# nixie_main_controller_board_0_2_1.net
KiCad netlist of a schematic drawn in EAGLE
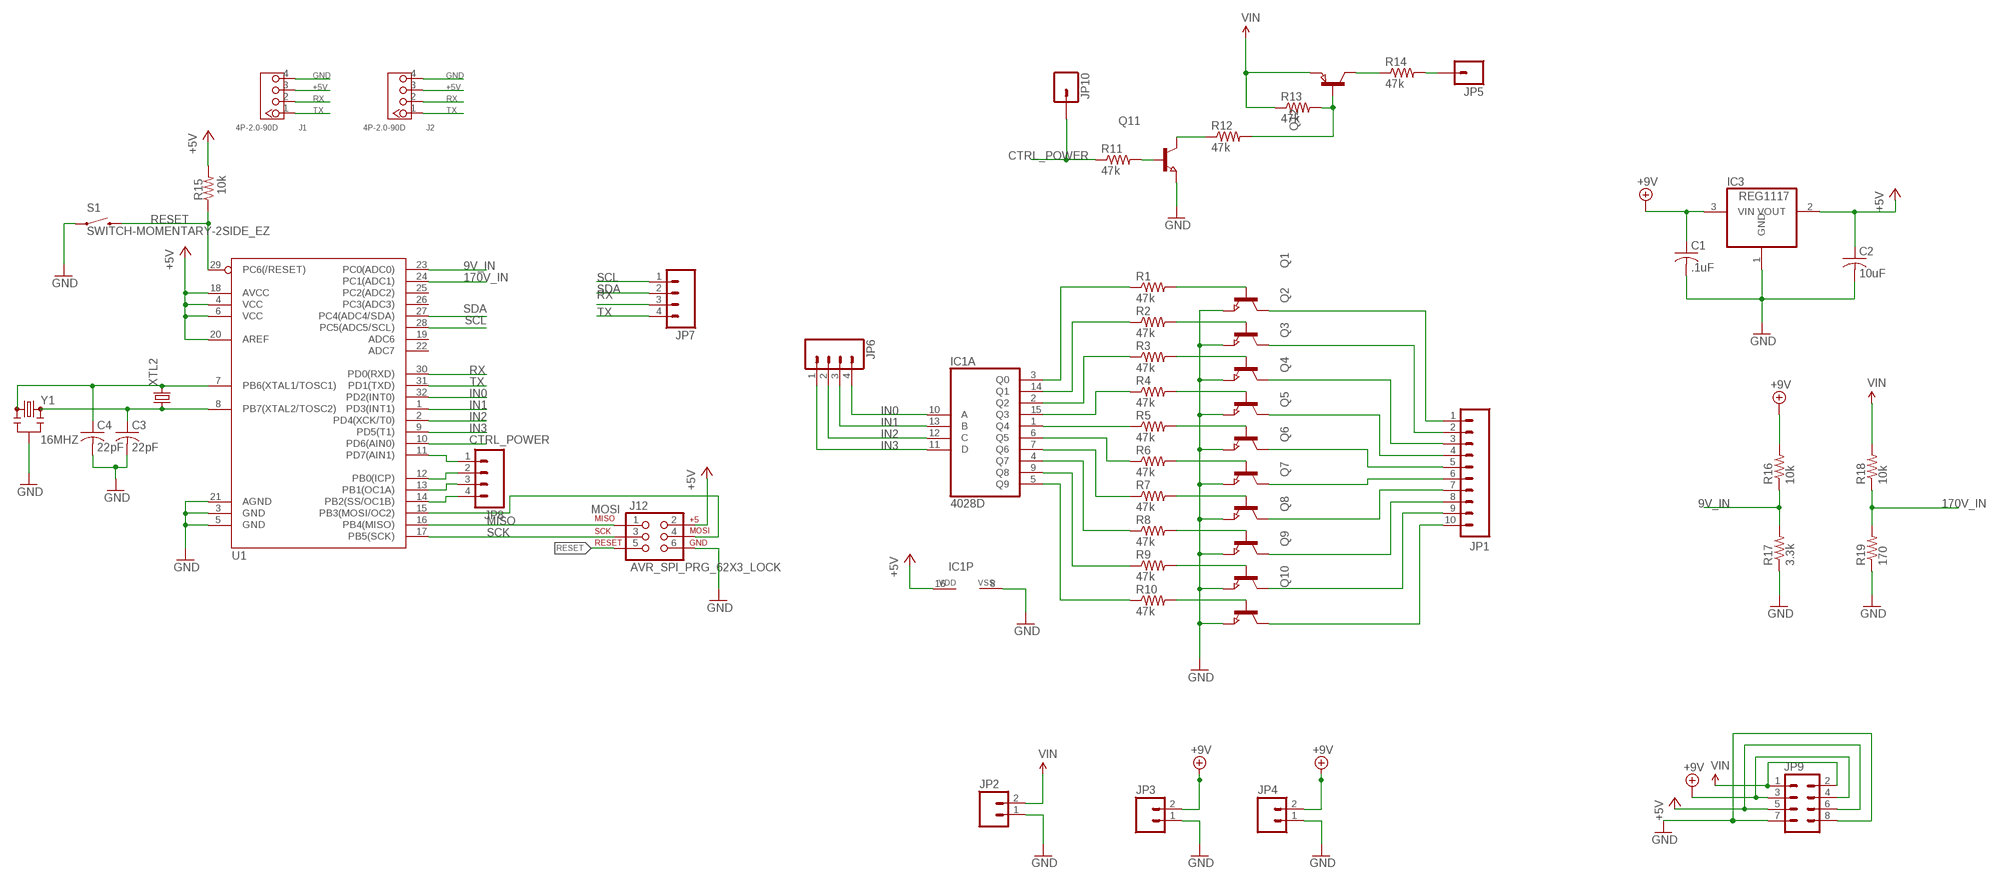
[diagram p0: schematic, sheet 1]

(export (version "E")
  (design (tool "Eeschema 10.0.6"))
  (components
    (comp (ref "C1")
      (value ".1uF")
      (footprint "eagle-import:C0603")
      (libsource (lib "eagle-import") (part "C-USC0603"))
    )
    (comp (ref "C2")
      (value "10uF")
      (footprint "eagle-import:C0805")
      (libsource (lib "eagle-import") (part "C-USC0805"))
    )
    (comp (ref "C3")
      (value "22pF")
      (footprint "eagle-import:C0603")
      (libsource (lib "eagle-import") (part "C-USC0603"))
    )
    (comp (ref "C4")
      (value "22pF")
      (footprint "eagle-import:C0603")
      (libsource (lib "eagle-import") (part "C-USC0603"))
    )
    (comp (ref "IC1")
      (value "4028D")
      (footprint "eagle-import:SO16")
      (libsource (lib "eagle-import") (part "4028D"))
    )
    (comp (ref "IC3")
      (value "REG1117")
      (footprint "eagle-import:SOT223")
      (libsource (lib "eagle-import") (part "REG1117"))
    )
    (comp (ref "J1")
      (value "4P-2.0-90D")
      (footprint "eagle-import:HW4-2.0-90D")
      (libsource (lib "eagle-import") (part "GROVE-CONNECTOR-DIP-90D(4P-2.0)"))
    )
    (comp (ref "J2")
      (value "4P-2.0-90D")
      (footprint "eagle-import:HW4-2.0-90D")
      (libsource (lib "eagle-import") (part "GROVE-CONNECTOR-DIP-90D(4P-2.0)"))
    )
    (comp (ref "J12")
      (value "AVR_SPI_PRG_62X3_LOCK")
      (footprint "eagle-import:2X3_LOCK")
      (libsource (lib "eagle-import") (part "AVR_SPI_PRG_62X3_LOCK"))
    )
    (comp (ref "JP1")
      (value "M10LOCK")
      (footprint "eagle-import:1X10_LOCK")
      (libsource (lib "eagle-import") (part "M10LOCK"))
    )
    (comp (ref "JP2")
      (value "M02LOCK")
      (footprint "eagle-import:1X02_LOCK")
      (libsource (lib "eagle-import") (part "M02LOCK"))
    )
    (comp (ref "JP3")
      (value "M02LOCK")
      (footprint "eagle-import:1X02_LOCK")
      (libsource (lib "eagle-import") (part "M02LOCK"))
    )
    (comp (ref "JP4")
      (value "M02LOCK")
      (footprint "eagle-import:1X02_LOCK")
      (libsource (lib "eagle-import") (part "M02LOCK"))
    )
    (comp (ref "JP5")
      (value "M01PTH")
      (footprint "eagle-import:1X01")
      (libsource (lib "eagle-import") (part "M01PTH"))
    )
    (comp (ref "JP6")
      (value "M04PTH")
      (footprint "eagle-import:1X04")
      (libsource (lib "eagle-import") (part "M04PTH"))
    )
    (comp (ref "JP7")
      (value "M04PTH")
      (footprint "eagle-import:1X04")
      (libsource (lib "eagle-import") (part "M04PTH"))
    )
    (comp (ref "JP8")
      (value "M04PTH")
      (footprint "eagle-import:1X04")
      (libsource (lib "eagle-import") (part "M04PTH"))
    )
    (comp (ref "JP9")
      (value "M04X2")
      (footprint "eagle-import:2X4")
      (libsource (lib "eagle-import") (part "M04X2"))
    )
    (comp (ref "JP10")
      (value "M01PTH")
      (footprint "eagle-import:1X01")
      (libsource (lib "eagle-import") (part "M01PTH"))
    )
    (comp (ref "Q1")
      (value "NPN-TRANSISTOR_SOT23")
      (footprint "eagle-import:SOT23")
      (libsource (lib "eagle-import") (part "NPN-TRANSISTOR_SOT23"))
    )
    (comp (ref "Q2")
      (value "NPN-TRANSISTOR_SOT23")
      (footprint "eagle-import:SOT23")
      (libsource (lib "eagle-import") (part "NPN-TRANSISTOR_SOT23"))
    )
    (comp (ref "Q3")
      (value "NPN-TRANSISTOR_SOT23")
      (footprint "eagle-import:SOT23")
      (libsource (lib "eagle-import") (part "NPN-TRANSISTOR_SOT23"))
    )
    (comp (ref "Q4")
      (value "NPN-TRANSISTOR_SOT23")
      (footprint "eagle-import:SOT23")
      (libsource (lib "eagle-import") (part "NPN-TRANSISTOR_SOT23"))
    )
    (comp (ref "Q5")
      (value "NPN-TRANSISTOR_SOT23")
      (footprint "eagle-import:SOT23")
      (libsource (lib "eagle-import") (part "NPN-TRANSISTOR_SOT23"))
    )
    (comp (ref "Q6")
      (value "NPN-TRANSISTOR_SOT23")
      (footprint "eagle-import:SOT23")
      (libsource (lib "eagle-import") (part "NPN-TRANSISTOR_SOT23"))
    )
    (comp (ref "Q7")
      (value "NPN-TRANSISTOR_SOT23")
      (footprint "eagle-import:SOT23")
      (libsource (lib "eagle-import") (part "NPN-TRANSISTOR_SOT23"))
    )
    (comp (ref "Q8")
      (value "NPN-TRANSISTOR_SOT23")
      (footprint "eagle-import:SOT23")
      (libsource (lib "eagle-import") (part "NPN-TRANSISTOR_SOT23"))
    )
    (comp (ref "Q9")
      (value "NPN-TRANSISTOR_SOT23")
      (footprint "eagle-import:SOT23")
      (libsource (lib "eagle-import") (part "NPN-TRANSISTOR_SOT23"))
    )
    (comp (ref "Q10")
      (value "NPN-TRANSISTOR_SOT23")
      (footprint "eagle-import:SOT23")
      (libsource (lib "eagle-import") (part "NPN-TRANSISTOR_SOT23"))
    )
    (comp (ref "Q11")
      (value "NPN-TRANSISTOR_SOT23")
      (footprint "eagle-import:SOT23")
      (libsource (lib "eagle-import") (part "NPN-TRANSISTOR_SOT23"))
    )
    (comp (ref "Q12")
      (value "PNP-TRANSISTOR_SOT23")
      (footprint "eagle-import:SOT23")
      (libsource (lib "eagle-import") (part "PNP-TRANSISTOR_SOT23"))
    )
    (comp (ref "R1")
      (value "47k")
      (footprint "eagle-import:R0603")
      (libsource (lib "eagle-import") (part "R-US_R0603"))
    )
    (comp (ref "R2")
      (value "47k")
      (footprint "eagle-import:R0603")
      (libsource (lib "eagle-import") (part "R-US_R0603"))
    )
    (comp (ref "R3")
      (value "47k")
      (footprint "eagle-import:R0603")
      (libsource (lib "eagle-import") (part "R-US_R0603"))
    )
    (comp (ref "R4")
      (value "47k")
      (footprint "eagle-import:R0603")
      (libsource (lib "eagle-import") (part "R-US_R0603"))
    )
    (comp (ref "R5")
      (value "47k")
      (footprint "eagle-import:R0603")
      (libsource (lib "eagle-import") (part "R-US_R0603"))
    )
    (comp (ref "R6")
      (value "47k")
      (footprint "eagle-import:R0603")
      (libsource (lib "eagle-import") (part "R-US_R0603"))
    )
    (comp (ref "R7")
      (value "47k")
      (footprint "eagle-import:R0603")
      (libsource (lib "eagle-import") (part "R-US_R0603"))
    )
    (comp (ref "R8")
      (value "47k")
      (footprint "eagle-import:R0603")
      (libsource (lib "eagle-import") (part "R-US_R0603"))
    )
    (comp (ref "R9")
      (value "47k")
      (footprint "eagle-import:R0603")
      (libsource (lib "eagle-import") (part "R-US_R0603"))
    )
    (comp (ref "R10")
      (value "47k")
      (footprint "eagle-import:R0603")
      (libsource (lib "eagle-import") (part "R-US_R0603"))
    )
    (comp (ref "R11")
      (value "47k")
      (footprint "eagle-import:R0603")
      (libsource (lib "eagle-import") (part "R-US_R0603"))
    )
    (comp (ref "R12")
      (value "47k")
      (footprint "eagle-import:R0603")
      (libsource (lib "eagle-import") (part "R-US_R0603"))
    )
    (comp (ref "R13")
      (value "47k")
      (footprint "eagle-import:R0603")
      (libsource (lib "eagle-import") (part "R-US_R0603"))
    )
    (comp (ref "R14")
      (value "47k")
      (footprint "eagle-import:R0603")
      (libsource (lib "eagle-import") (part "R-US_R0603"))
    )
    (comp (ref "R15")
      (value "10k")
      (footprint "eagle-import:0603")
      (libsource (lib "eagle-import") (part "RESISTOR0603-RES"))
    )
    (comp (ref "R16")
      (value "10k")
      (footprint "eagle-import:R0603")
      (libsource (lib "eagle-import") (part "R-US_R0603"))
    )
    (comp (ref "R17")
      (value "3.3k")
      (footprint "eagle-import:R0603")
      (libsource (lib "eagle-import") (part "R-US_R0603"))
    )
    (comp (ref "R18")
      (value "10k")
      (footprint "eagle-import:R0603")
      (libsource (lib "eagle-import") (part "R-US_R0603"))
    )
    (comp (ref "R19")
      (value "170")
      (footprint "eagle-import:R0603")
      (libsource (lib "eagle-import") (part "R-US_R0603"))
    )
    (comp (ref "S1")
      (value "SWITCH-MOMENTARY-2SIDE_EZ")
      (footprint "eagle-import:TACTILE-PTH-SIDEEZ")
      (libsource (lib "eagle-import") (part "SWITCH-MOMENTARY-2SIDE_EZ"))
    )
    (comp (ref "U1")
      (value "ATMEGA328_SMT")
      (footprint "eagle-import:TQFP32-08")
      (libsource (lib "eagle-import") (part "ATMEGA328_SMT"))
    )
    (comp (ref "XTL2")
      (value "CRYSTALHC49S")
      (footprint "eagle-import:HC49_S")
      (libsource (lib "eagle-import") (part "CRYSTALHC49S"))
    )
    (comp (ref "Y1")
      (value "16MHZ")
      (footprint "eagle-import:RESONATOR-SMD")
      (libsource (lib "eagle-import") (part "RESONATOR16MHZ"))
    )
  )
  (nets
    (net (code "1") (name "+5V") (class "Default")
      (node (ref "C2") (pin "1") (pinfunction "1_1") (pintype "passive"))
      (node (ref "IC1") (pin "16") (pinfunction "VDD_16") (pintype "power_in"))
      (node (ref "IC3") (pin "2") (pinfunction "VOUT_2") (pintype "output"))
      (node (ref "J1") (pin "3") (pinfunction "3_3") (pintype "bidirectional"))
      (node (ref "J12") (pin "2") (pinfunction "2_2") (pintype "passive"))
      (node (ref "J2") (pin "3") (pinfunction "3_3") (pintype "bidirectional"))
      (node (ref "JP9") (pin "5") (pinfunction "5_5") (pintype "passive"))
      (node (ref "JP9") (pin "6") (pinfunction "6_6") (pintype "passive"))
      (node (ref "R15") (pin "2") (pinfunction "2_2") (pintype "passive"))
      (node (ref "U1") (pin "18") (pinfunction "AVCC_18") (pintype "bidirectional"))
      (node (ref "U1") (pin "20") (pinfunction "AREF_20") (pintype "bidirectional"))
      (node (ref "U1") (pin "4") (pinfunction "VCC_4") (pintype "bidirectional"))
      (node (ref "U1") (pin "6") (pinfunction "VCC_6") (pintype "bidirectional"))
    )
    (net (code "2") (name "+9V") (class "Default")
      (node (ref "C1") (pin "1") (pinfunction "1_1") (pintype "passive"))
      (node (ref "IC3") (pin "3") (pinfunction "VIN_3") (pintype "input"))
      (node (ref "JP3") (pin "2") (pinfunction "2_2") (pintype "passive"))
      (node (ref "JP4") (pin "2") (pinfunction "2_2") (pintype "passive"))
      (node (ref "JP9") (pin "3") (pinfunction "3_3") (pintype "passive"))
      (node (ref "JP9") (pin "4") (pinfunction "4_4") (pintype "passive"))
      (node (ref "R16") (pin "2") (pinfunction "2_2") (pintype "passive"))
    )
    (net (code "3") (name "/9V_IN") (class "Default")
      (node (ref "R16") (pin "1") (pinfunction "1_1") (pintype "passive"))
      (node (ref "R17") (pin "2") (pinfunction "2_2") (pintype "passive"))
      (node (ref "U1") (pin "23") (pinfunction "PC0(ADC0)_23") (pintype "bidirectional"))
    )
    (net (code "4") (name "/170V_IN") (class "Default")
      (node (ref "R18") (pin "1") (pinfunction "1_1") (pintype "passive"))
      (node (ref "R19") (pin "2") (pinfunction "2_2") (pintype "passive"))
      (node (ref "U1") (pin "24") (pinfunction "PC1(ADC1)_24") (pintype "bidirectional"))
    )
    (net (code "5") (name "/CTRL_POWER") (class "Default")
      (node (ref "JP10") (pin "1") (pinfunction "1_1") (pintype "passive"))
      (node (ref "R11") (pin "1") (pinfunction "1_1") (pintype "passive"))
      (node (ref "U1") (pin "10") (pinfunction "PD6(AIN0)_10") (pintype "bidirectional"))
    )
    (net (code "6") (name "/IN0") (class "Default")
      (node (ref "IC1") (pin "10") (pinfunction "A_10") (pintype "input"))
      (node (ref "JP6") (pin "4") (pinfunction "4_4") (pintype "passive"))
      (node (ref "U1") (pin "32") (pinfunction "PD2(INT0)_32") (pintype "bidirectional"))
    )
    (net (code "7") (name "/IN1") (class "Default")
      (node (ref "IC1") (pin "13") (pinfunction "B_13") (pintype "input"))
      (node (ref "JP6") (pin "3") (pinfunction "3_3") (pintype "passive"))
      (node (ref "U1") (pin "1") (pinfunction "PD3(INT1)_1") (pintype "bidirectional"))
    )
    (net (code "8") (name "/IN2") (class "Default")
      (node (ref "IC1") (pin "12") (pinfunction "C_12") (pintype "input"))
      (node (ref "JP6") (pin "2") (pinfunction "2_2") (pintype "passive"))
      (node (ref "U1") (pin "2") (pinfunction "PD4(XCK/T0)_2") (pintype "bidirectional"))
    )
    (net (code "9") (name "/IN3") (class "Default")
      (node (ref "IC1") (pin "11") (pinfunction "D_11") (pintype "input"))
      (node (ref "JP6") (pin "1") (pinfunction "1_1") (pintype "passive"))
      (node (ref "U1") (pin "9") (pinfunction "PD5(T1)_9") (pintype "bidirectional"))
    )
    (net (code "10") (name "/MISO") (class "Default")
      (node (ref "J12") (pin "1") (pinfunction "1_1") (pintype "passive"))
      (node (ref "U1") (pin "16") (pinfunction "PB4(MISO)_16") (pintype "bidirectional"))
    )
    (net (code "11") (name "/MOSI") (class "Default")
      (node (ref "J12") (pin "4") (pinfunction "4_4") (pintype "passive"))
      (node (ref "U1") (pin "15") (pinfunction "PB3(MOSI/OC2)_15") (pintype "bidirectional"))
    )
    (net (code "12") (name "/RX") (class "Default")
      (node (ref "J1") (pin "2") (pinfunction "2_2") (pintype "bidirectional"))
      (node (ref "J2") (pin "2") (pinfunction "2_2") (pintype "bidirectional"))
      (node (ref "JP7") (pin "3") (pinfunction "3_3") (pintype "passive"))
      (node (ref "U1") (pin "30") (pinfunction "PD0(RXD)_30") (pintype "bidirectional"))
    )
    (net (code "13") (name "/SCK") (class "Default")
      (node (ref "J12") (pin "3") (pinfunction "3_3") (pintype "passive"))
      (node (ref "U1") (pin "17") (pinfunction "PB5(SCK)_17") (pintype "bidirectional"))
    )
    (net (code "14") (name "/SCL") (class "Default")
      (node (ref "JP7") (pin "1") (pinfunction "1_1") (pintype "passive"))
      (node (ref "U1") (pin "28") (pinfunction "PC5(ADC5/SCL)_28") (pintype "bidirectional"))
    )
    (net (code "15") (name "/SDA") (class "Default")
      (node (ref "JP7") (pin "2") (pinfunction "2_2") (pintype "passive"))
      (node (ref "U1") (pin "27") (pinfunction "PC4(ADC4/SDA)_27") (pintype "bidirectional"))
    )
    (net (code "16") (name "/TX") (class "Default")
      (node (ref "J1") (pin "1") (pinfunction "1_1") (pintype "bidirectional"))
      (node (ref "J2") (pin "1") (pinfunction "1_1") (pintype "bidirectional"))
      (node (ref "JP7") (pin "4") (pinfunction "4_4") (pintype "passive"))
      (node (ref "U1") (pin "31") (pinfunction "PD1(TXD)_31") (pintype "bidirectional"))
    )
    (net (code "17") (name "GND") (class "Default")
      (node (ref "C1") (pin "2") (pinfunction "2_2") (pintype "passive"))
      (node (ref "C2") (pin "2") (pinfunction "2_2") (pintype "passive"))
      (node (ref "C3") (pin "2") (pinfunction "2_2") (pintype "passive"))
      (node (ref "C4") (pin "2") (pinfunction "2_2") (pintype "passive"))
      (node (ref "IC1") (pin "8") (pinfunction "VSS_8") (pintype "power_in"))
      (node (ref "IC3") (pin "1") (pinfunction "GND_1") (pintype "power_in"))
      (node (ref "J1") (pin "4") (pinfunction "4_4") (pintype "bidirectional"))
      (node (ref "J12") (pin "6") (pinfunction "6_6") (pintype "passive"))
      (node (ref "J2") (pin "4") (pinfunction "4_4") (pintype "bidirectional"))
      (node (ref "JP2") (pin "1") (pinfunction "1_1") (pintype "passive"))
      (node (ref "JP3") (pin "1") (pinfunction "1_1") (pintype "passive"))
      (node (ref "JP4") (pin "1") (pinfunction "1_1") (pintype "passive"))
      (node (ref "JP9") (pin "7") (pinfunction "7_7") (pintype "passive"))
      (node (ref "JP9") (pin "8") (pinfunction "8_8") (pintype "passive"))
      (node (ref "Q1") (pin "2") (pinfunction "E_2") (pintype "passive"))
      (node (ref "Q10") (pin "2") (pinfunction "E_2") (pintype "passive"))
      (node (ref "Q11") (pin "2") (pinfunction "E_2") (pintype "passive"))
      (node (ref "Q2") (pin "2") (pinfunction "E_2") (pintype "passive"))
      (node (ref "Q3") (pin "2") (pinfunction "E_2") (pintype "passive"))
      (node (ref "Q4") (pin "2") (pinfunction "E_2") (pintype "passive"))
      (node (ref "Q5") (pin "2") (pinfunction "E_2") (pintype "passive"))
      (node (ref "Q6") (pin "2") (pinfunction "E_2") (pintype "passive"))
      (node (ref "Q7") (pin "2") (pinfunction "E_2") (pintype "passive"))
      (node (ref "Q8") (pin "2") (pinfunction "E_2") (pintype "passive"))
      (node (ref "Q9") (pin "2") (pinfunction "E_2") (pintype "passive"))
      (node (ref "R17") (pin "1") (pinfunction "1_1") (pintype "passive"))
      (node (ref "R19") (pin "1") (pinfunction "1_1") (pintype "passive"))
      (node (ref "S1") (pin "1") (pinfunction "1_1") (pintype "passive"))
      (node (ref "U1") (pin "21") (pinfunction "AGND_21") (pintype "bidirectional"))
      (node (ref "U1") (pin "3") (pinfunction "GND_3") (pintype "bidirectional"))
      (node (ref "U1") (pin "5") (pinfunction "GND_5") (pintype "bidirectional"))
      (node (ref "Y1") (pin "2") (pinfunction "2_2") (pintype "passive"))
    )
    (net (code "18") (name "Net-(IC1A-Q0)") (class "Default")
      (node (ref "IC1") (pin "3") (pinfunction "Q0_3") (pintype "output"))
      (node (ref "R1") (pin "1") (pinfunction "1_1") (pintype "passive"))
    )
    (net (code "19") (name "Net-(IC1A-Q1)") (class "Default")
      (node (ref "IC1") (pin "14") (pinfunction "Q1_14") (pintype "output"))
      (node (ref "R2") (pin "1") (pinfunction "1_1") (pintype "passive"))
    )
    (net (code "20") (name "Net-(IC1A-Q2)") (class "Default")
      (node (ref "IC1") (pin "2") (pinfunction "Q2_2") (pintype "output"))
      (node (ref "R3") (pin "1") (pinfunction "1_1") (pintype "passive"))
    )
    (net (code "21") (name "Net-(IC1A-Q3)") (class "Default")
      (node (ref "IC1") (pin "15") (pinfunction "Q3_15") (pintype "output"))
      (node (ref "R4") (pin "1") (pinfunction "1_1") (pintype "passive"))
    )
    (net (code "22") (name "Net-(IC1A-Q4)") (class "Default")
      (node (ref "IC1") (pin "1") (pinfunction "Q4_1") (pintype "output"))
      (node (ref "R5") (pin "1") (pinfunction "1_1") (pintype "passive"))
    )
    (net (code "23") (name "Net-(IC1A-Q5)") (class "Default")
      (node (ref "IC1") (pin "6") (pinfunction "Q5_6") (pintype "output"))
      (node (ref "R6") (pin "1") (pinfunction "1_1") (pintype "passive"))
    )
    (net (code "24") (name "Net-(IC1A-Q6)") (class "Default")
      (node (ref "IC1") (pin "7") (pinfunction "Q6_7") (pintype "output"))
      (node (ref "R7") (pin "1") (pinfunction "1_1") (pintype "passive"))
    )
    (net (code "25") (name "Net-(IC1A-Q7)") (class "Default")
      (node (ref "IC1") (pin "4") (pinfunction "Q7_4") (pintype "output"))
      (node (ref "R8") (pin "1") (pinfunction "1_1") (pintype "passive"))
    )
    (net (code "26") (name "Net-(IC1A-Q8)") (class "Default")
      (node (ref "IC1") (pin "9") (pinfunction "Q8_9") (pintype "output"))
      (node (ref "R9") (pin "1") (pinfunction "1_1") (pintype "passive"))
    )
    (net (code "27") (name "Net-(IC1A-Q9)") (class "Default")
      (node (ref "IC1") (pin "5") (pinfunction "Q9_5") (pintype "output"))
      (node (ref "R10") (pin "1") (pinfunction "1_1") (pintype "passive"))
    )
    (net (code "28") (name "Net-(JP5-Pad1)") (class "Default")
      (node (ref "JP5") (pin "1") (pinfunction "1_1") (pintype "passive"))
      (node (ref "R14") (pin "2") (pinfunction "2_2") (pintype "passive"))
    )
    (net (code "29") (name "Net-(Q1-B)") (class "Default")
      (node (ref "Q1") (pin "1") (pinfunction "B_1") (pintype "passive"))
      (node (ref "R1") (pin "2") (pinfunction "2_2") (pintype "passive"))
    )
    (net (code "30") (name "Net-(Q1-C)") (class "Default")
      (node (ref "JP1") (pin "1") (pinfunction "1_1") (pintype "passive"))
      (node (ref "Q1") (pin "3") (pinfunction "C_3") (pintype "passive"))
    )
    (net (code "31") (name "Net-(Q2-B)") (class "Default")
      (node (ref "Q2") (pin "1") (pinfunction "B_1") (pintype "passive"))
      (node (ref "R2") (pin "2") (pinfunction "2_2") (pintype "passive"))
    )
    (net (code "32") (name "Net-(Q2-C)") (class "Default")
      (node (ref "JP1") (pin "2") (pinfunction "2_2") (pintype "passive"))
      (node (ref "Q2") (pin "3") (pinfunction "C_3") (pintype "passive"))
    )
    (net (code "33") (name "Net-(Q3-B)") (class "Default")
      (node (ref "Q3") (pin "1") (pinfunction "B_1") (pintype "passive"))
      (node (ref "R3") (pin "2") (pinfunction "2_2") (pintype "passive"))
    )
    (net (code "34") (name "Net-(Q3-C)") (class "Default")
      (node (ref "JP1") (pin "3") (pinfunction "3_3") (pintype "passive"))
      (node (ref "Q3") (pin "3") (pinfunction "C_3") (pintype "passive"))
    )
    (net (code "35") (name "Net-(Q4-B)") (class "Default")
      (node (ref "Q4") (pin "1") (pinfunction "B_1") (pintype "passive"))
      (node (ref "R4") (pin "2") (pinfunction "2_2") (pintype "passive"))
    )
    (net (code "36") (name "Net-(Q4-C)") (class "Default")
      (node (ref "JP1") (pin "4") (pinfunction "4_4") (pintype "passive"))
      (node (ref "Q4") (pin "3") (pinfunction "C_3") (pintype "passive"))
    )
    (net (code "37") (name "Net-(Q5-B)") (class "Default")
      (node (ref "Q5") (pin "1") (pinfunction "B_1") (pintype "passive"))
      (node (ref "R5") (pin "2") (pinfunction "2_2") (pintype "passive"))
    )
    (net (code "38") (name "Net-(Q5-C)") (class "Default")
      (node (ref "JP1") (pin "5") (pinfunction "5_5") (pintype "passive"))
      (node (ref "Q5") (pin "3") (pinfunction "C_3") (pintype "passive"))
    )
    (net (code "39") (name "Net-(Q6-B)") (class "Default")
      (node (ref "Q6") (pin "1") (pinfunction "B_1") (pintype "passive"))
      (node (ref "R6") (pin "2") (pinfunction "2_2") (pintype "passive"))
    )
    (net (code "40") (name "Net-(Q6-C)") (class "Default")
      (node (ref "JP1") (pin "6") (pinfunction "6_6") (pintype "passive"))
      (node (ref "Q6") (pin "3") (pinfunction "C_3") (pintype "passive"))
    )
    (net (code "41") (name "Net-(Q7-B)") (class "Default")
      (node (ref "Q7") (pin "1") (pinfunction "B_1") (pintype "passive"))
      (node (ref "R7") (pin "2") (pinfunction "2_2") (pintype "passive"))
    )
    (net (code "42") (name "Net-(Q7-C)") (class "Default")
      (node (ref "JP1") (pin "7") (pinfunction "7_7") (pintype "passive"))
      (node (ref "Q7") (pin "3") (pinfunction "C_3") (pintype "passive"))
    )
    (net (code "43") (name "Net-(Q8-B)") (class "Default")
      (node (ref "Q8") (pin "1") (pinfunction "B_1") (pintype "passive"))
      (node (ref "R8") (pin "2") (pinfunction "2_2") (pintype "passive"))
    )
    (net (code "44") (name "Net-(Q8-C)") (class "Default")
      (node (ref "JP1") (pin "8") (pinfunction "8_8") (pintype "passive"))
      (node (ref "Q8") (pin "3") (pinfunction "C_3") (pintype "passive"))
    )
    (net (code "45") (name "Net-(Q9-B)") (class "Default")
      (node (ref "Q9") (pin "1") (pinfunction "B_1") (pintype "passive"))
      (node (ref "R9") (pin "2") (pinfunction "2_2") (pintype "passive"))
    )
    (net (code "46") (name "Net-(Q9-C)") (class "Default")
      (node (ref "JP1") (pin "9") (pinfunction "9_9") (pintype "passive"))
      (node (ref "Q9") (pin "3") (pinfunction "C_3") (pintype "passive"))
    )
    (net (code "47") (name "Net-(Q10-B)") (class "Default")
      (node (ref "Q10") (pin "1") (pinfunction "B_1") (pintype "passive"))
      (node (ref "R10") (pin "2") (pinfunction "2_2") (pintype "passive"))
    )
    (net (code "48") (name "Net-(Q10-C)") (class "Default")
      (node (ref "JP1") (pin "10") (pinfunction "10_10") (pintype "passive"))
      (node (ref "Q10") (pin "3") (pinfunction "C_3") (pintype "passive"))
    )
    (net (code "49") (name "Net-(Q11-B)") (class "Default")
      (node (ref "Q11") (pin "1") (pinfunction "B_1") (pintype "passive"))
      (node (ref "R11") (pin "2") (pinfunction "2_2") (pintype "passive"))
    )
    (net (code "50") (name "Net-(Q11-C)") (class "Default")
      (node (ref "Q11") (pin "3") (pinfunction "C_3") (pintype "passive"))
      (node (ref "R12") (pin "1") (pinfunction "1_1") (pintype "passive"))
    )
    (net (code "51") (name "Net-(Q12-B)") (class "Default")
      (node (ref "Q12") (pin "1") (pinfunction "B_1") (pintype "passive"))
      (node (ref "R12") (pin "2") (pinfunction "2_2") (pintype "passive"))
      (node (ref "R13") (pin "2") (pinfunction "2_2") (pintype "passive"))
    )
    (net (code "52") (name "Net-(Q12-C)") (class "Default")
      (node (ref "Q12") (pin "3") (pinfunction "C_3") (pintype "passive"))
      (node (ref "R14") (pin "1") (pinfunction "1_1") (pintype "passive"))
    )
    (net (code "53") (name "Net-(U1-PB0(ICP))") (class "Default")
      (node (ref "JP8") (pin "2") (pinfunction "2_2") (pintype "passive"))
      (node (ref "U1") (pin "12") (pinfunction "PB0(ICP)_12") (pintype "bidirectional"))
    )
    (net (code "54") (name "Net-(U1-PB1(OC1A))") (class "Default")
      (node (ref "JP8") (pin "3") (pinfunction "3_3") (pintype "passive"))
      (node (ref "U1") (pin "13") (pinfunction "PB1(OC1A)_13") (pintype "bidirectional"))
    )
    (net (code "55") (name "Net-(U1-PB2(SS{slash}OC1B))") (class "Default")
      (node (ref "JP8") (pin "4") (pinfunction "4_4") (pintype "passive"))
      (node (ref "U1") (pin "14") (pinfunction "PB2(SS/OC1B)_14") (pintype "bidirectional"))
    )
    (net (code "56") (name "Net-(U1-PB6(XTAL1{slash}TOSC1))") (class "Default")
      (node (ref "C4") (pin "1") (pinfunction "1_1") (pintype "passive"))
      (node (ref "U1") (pin "7") (pinfunction "PB6(XTAL1/TOSC1)_7") (pintype "bidirectional"))
      (node (ref "XTL2") (pin "2") (pinfunction "2_2") (pintype "passive"))
      (node (ref "Y1") (pin "1") (pinfunction "1_1") (pintype "passive"))
    )
    (net (code "57") (name "Net-(U1-PB7(XTAL2{slash}TOSC2))") (class "Default")
      (node (ref "C3") (pin "1") (pinfunction "1_1") (pintype "passive"))
      (node (ref "U1") (pin "8") (pinfunction "PB7(XTAL2/TOSC2)_8") (pintype "bidirectional"))
      (node (ref "XTL2") (pin "1") (pinfunction "1_1") (pintype "passive"))
      (node (ref "Y1") (pin "3") (pinfunction "3_3") (pintype "passive"))
    )
    (net (code "58") (name "Net-(U1-PD7(AIN1))") (class "Default")
      (node (ref "JP8") (pin "1") (pinfunction "1_1") (pintype "passive"))
      (node (ref "U1") (pin "11") (pinfunction "PD7(AIN1)_11") (pintype "bidirectional"))
    )
    (net (code "59") (name "RESET") (class "Default")
      (node (ref "J12") (pin "5") (pinfunction "5_5") (pintype "passive"))
      (node (ref "R15") (pin "1") (pinfunction "1_1") (pintype "passive"))
      (node (ref "S1") (pin "2") (pinfunction "2_2") (pintype "passive"))
      (node (ref "U1") (pin "29") (pinfunction "PC6(/RESET)_29") (pintype "bidirectional"))
    )
    (net (code "60") (name "VIN") (class "Default")
      (node (ref "JP2") (pin "2") (pinfunction "2_2") (pintype "passive"))
      (node (ref "JP9") (pin "1") (pinfunction "1_1") (pintype "passive"))
      (node (ref "JP9") (pin "2") (pinfunction "2_2") (pintype "passive"))
      (node (ref "Q12") (pin "2") (pinfunction "E_2") (pintype "passive"))
      (node (ref "R13") (pin "1") (pinfunction "1_1") (pintype "passive"))
      (node (ref "R18") (pin "2") (pinfunction "2_2") (pintype "passive"))
    )
    (net (code "61") (name "unconnected-(U1-ADC6-Pad19)") (class "Default")
      (node (ref "U1") (pin "19") (pinfunction "ADC6_19") (pintype "bidirectional"))
    )
    (net (code "62") (name "unconnected-(U1-ADC7-Pad22)") (class "Default")
      (node (ref "U1") (pin "22") (pinfunction "ADC7_22") (pintype "bidirectional"))
    )
    (net (code "63") (name "unconnected-(U1-PC2(ADC2)-Pad25)") (class "Default")
      (node (ref "U1") (pin "25") (pinfunction "PC2(ADC2)_25") (pintype "bidirectional"))
    )
    (net (code "64") (name "unconnected-(U1-PC3(ADC3)-Pad26)") (class "Default")
      (node (ref "U1") (pin "26") (pinfunction "PC3(ADC3)_26") (pintype "bidirectional"))
    )
  )
)
